# cellular.net
KiCad netlist of a schematic drawn in Altium Designer
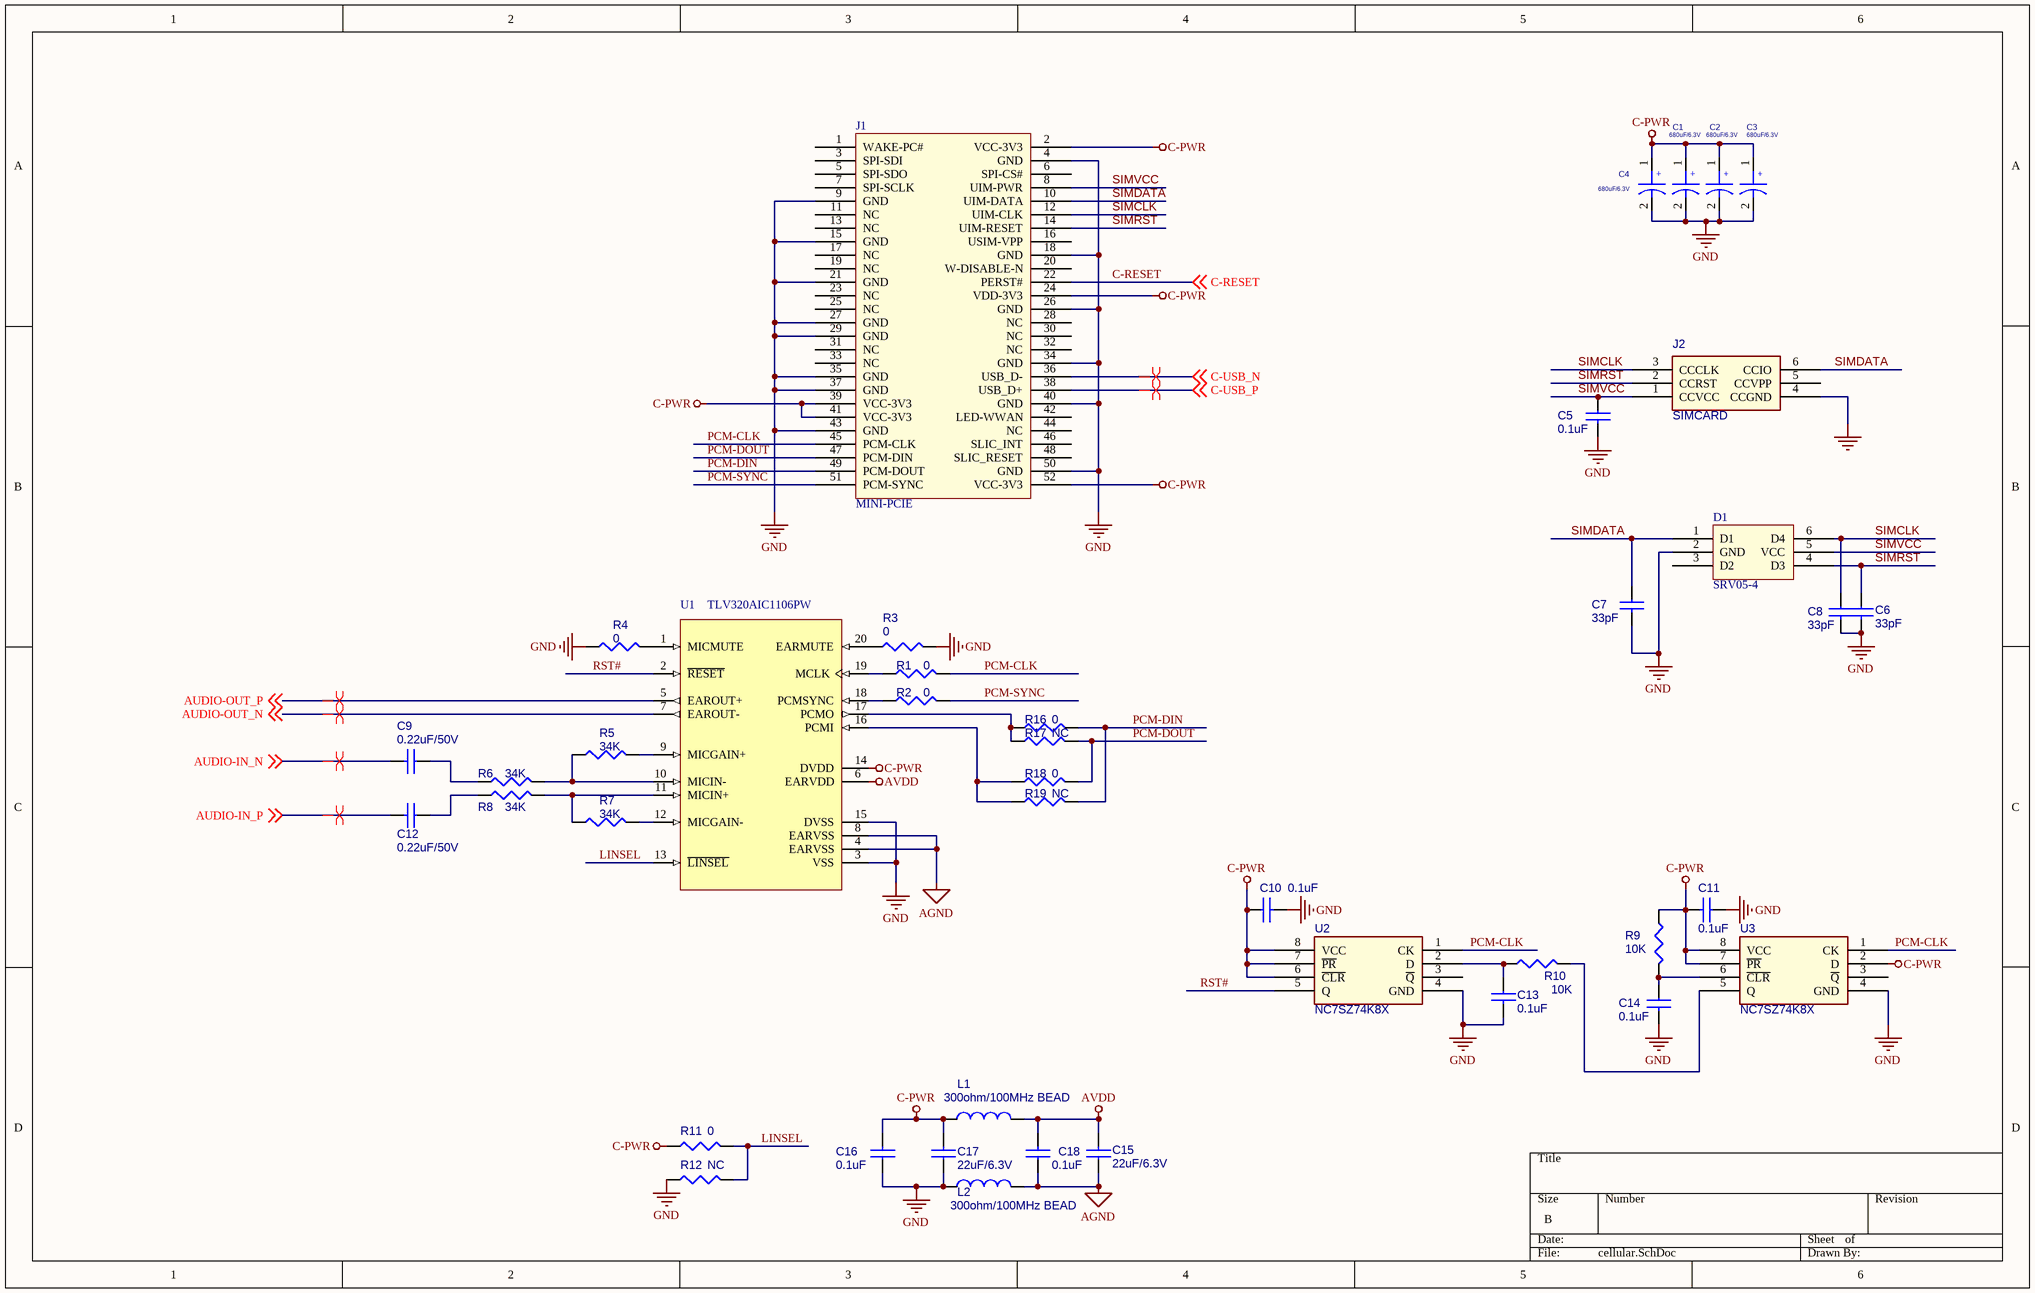
[diagram p0: cellular.SchDoc]

(export (version "E")
  (design (tool "Eeschema 10.0.6"))
  (components
    (comp (ref "C1")
      (value "680uF/6.3V")
      (footprint "7343")
      (description "CAP;10U  ,TT,20V ,20%,6032,SMT")
      (libsource (lib "*") (part "10U-6032-20V"))
    )
    (comp (ref "C2")
      (value "680uF/6.3V")
      (footprint "7343")
      (description "CAP;10U  ,TT,20V ,20%,6032,SMT")
      (libsource (lib "*") (part "10U-6032-20V"))
    )
    (comp (ref "C3")
      (value "680uF/6.3V")
      (footprint "7343")
      (description "CAP;10U  ,TT,20V ,20%,6032,SMT")
      (libsource (lib "*") (part "10U-6032-20V"))
    )
    (comp (ref "C4")
      (value "680uF/6.3V")
      (footprint "7343")
      (description "CAP;10U  ,TT,20V ,20%,6032,SMT")
      (libsource (lib "*") (part "10U-6032-20V"))
    )
    (comp (ref "C5") (value "0.1uF") (libsource (lib "*") (part "P_CAP NP")))
    (comp (ref "C6") (value "33pF") (libsource (lib "*") (part "P_CAP NP")))
    (comp (ref "C7") (value "33pF") (libsource (lib "*") (part "P_CAP NP")))
    (comp (ref "C8") (value "33pF") (libsource (lib "*") (part "P_CAP NP")))
    (comp (ref "C9") (value "0.22uF/50V") (footprint "0603") (libsource (lib "*") (part "P_CAP NP")))
    (comp (ref "C10") (value "0.1uF") (libsource (lib "*") (part "P_CAP NP")))
    (comp (ref "C11") (value "0.1uF") (libsource (lib "*") (part "P_CAP NP")))
    (comp (ref "C12") (value "0.22uF/50V") (footprint "0603") (libsource (lib "*") (part "P_CAP NP")))
    (comp (ref "C13") (value "0.1uF") (libsource (lib "*") (part "P_CAP NP")))
    (comp (ref "C14") (value "0.1uF") (libsource (lib "*") (part "P_CAP NP")))
    (comp (ref "C15") (value "22uF/6.3V") (libsource (lib "*") (part "P_CAP NP")))
    (comp (ref "C16") (value "0.1uF") (libsource (lib "*") (part "P_CAP NP")))
    (comp (ref "C17") (value "22uF/6.3V") (libsource (lib "*") (part "P_CAP NP")))
    (comp (ref "C18") (value "0.1uF") (libsource (lib "*") (part "P_CAP NP")))
    (comp (ref "D1") (value "SRV05-4") (footprint "SOT23-6") (libsource (lib "Schlib") (part "SRV05-4")))
    (comp (ref "J1") (value "MINI-PCIE") (libsource (lib "Schlib") (part "MINI-PCIE")))
    (comp (ref "J2") (value "SIMCARD") (footprint "SIMLOCK") (libsource (lib "*") (part "SIMCARD")))
    (comp (ref "L1") (value "300ohm/100MHz BEAD") (libsource (lib "*") (part "INDUCTOR_4")))
    (comp (ref "L2") (value "300ohm/100MHz BEAD") (libsource (lib "*") (part "INDUCTOR_4")))
    (comp (ref "R1") (value "0") (footprint "0603") (libsource (lib "*") (part "P_R")))
    (comp (ref "R2") (value "0") (footprint "0603") (libsource (lib "*") (part "P_R")))
    (comp (ref "R3") (value "0") (footprint "0603") (libsource (lib "*") (part "P_R")))
    (comp (ref "R4") (value "0") (footprint "0603") (libsource (lib "*") (part "P_R")))
    (comp (ref "R5") (value "34K") (footprint "0603") (libsource (lib "*") (part "P_R")))
    (comp (ref "R6") (value "34K") (footprint "0603") (libsource (lib "*") (part "P_R")))
    (comp (ref "R7") (value "34K") (footprint "0603") (libsource (lib "*") (part "P_R")))
    (comp (ref "R8") (value "34K") (footprint "0603") (libsource (lib "*") (part "P_R")))
    (comp (ref "R9") (value "10K") (footprint "0603") (libsource (lib "*") (part "P_R")))
    (comp (ref "R10") (value "10K") (footprint "0603") (libsource (lib "*") (part "P_R")))
    (comp (ref "R11") (value "0") (footprint "0603") (libsource (lib "*") (part "P_R")))
    (comp (ref "R12") (value "NC") (footprint "0603") (libsource (lib "*") (part "P_R")))
    (comp (ref "R16") (value "0") (footprint "0603") (libsource (lib "*") (part "P_R")))
    (comp (ref "R17") (value "NC") (footprint "0603") (libsource (lib "*") (part "P_R")))
    (comp (ref "R18") (value "0") (footprint "0603") (libsource (lib "*") (part "P_R")))
    (comp (ref "R19") (value "NC") (footprint "0603") (libsource (lib "*") (part "P_R")))
    (comp (ref "U1")
      (value "TLV320AIC1106PW")
      (footprint "PW020")
      (description "PCM CODEC With Microphone Amps & Speaker Driver, 20-Pin TSSOP")
      (fields (field (name "PUBLISHER") "Altium Limited"))
      (libsource (lib "TI Converter CODEC Voice-Band") (part "TLV320AIC1106PWG4"))
    )
    (comp (ref "U2")
      (value "NC7SZ74K8X")
      (footprint "US8")
      (description "IC;NC7SZ74,D-TYPE FLIP-FLOP,US8")
      (libsource (lib "*") (part "NC7SZ74-US8_0"))
    )
    (comp (ref "U3")
      (value "NC7SZ74K8X")
      (footprint "US8")
      (description "IC;NC7SZ74,D-TYPE FLIP-FLOP,US8")
      (libsource (lib "*") (part "NC7SZ74-US8_0"))
    )
  )
  (nets
    (net (code "1") (name "/LINSEL") (class "Default")
      (node (ref "R11") (pin "1") (pinfunction "1_1") (pintype "passive"))
      (node (ref "R12") (pin "1") (pinfunction "1_1") (pintype "passive"))
      (node (ref "U1") (pin "13") (pinfunction "~{LINSEL}_13") (pintype "input"))
    )
    (net (code "2") (name "/PCM-CLK") (class "Default")
      (node (ref "J1") (pin "45") (pinfunction "PCM-CLK_45") (pintype "passive"))
      (node (ref "R1") (pin "1") (pinfunction "1_1") (pintype "passive"))
      (node (ref "U2") (pin "1") (pinfunction "CK_1") (pintype "passive"))
      (node (ref "U3") (pin "1") (pinfunction "CK_1") (pintype "passive"))
    )
    (net (code "3") (name "/PCM-DIN") (class "Default")
      (node (ref "J1") (pin "49") (pinfunction "PCM-DOUT_49") (pintype "passive"))
      (node (ref "R16") (pin "1") (pinfunction "1_1") (pintype "passive"))
      (node (ref "R19") (pin "1") (pinfunction "1_1") (pintype "passive"))
    )
    (net (code "4") (name "/PCM-DOUT") (class "Default")
      (node (ref "J1") (pin "47") (pinfunction "PCM-DIN_47") (pintype "passive"))
      (node (ref "R17") (pin "1") (pinfunction "1_1") (pintype "passive"))
      (node (ref "R18") (pin "1") (pinfunction "1_1") (pintype "passive"))
    )
    (net (code "5") (name "/PCM-SYNC") (class "Default")
      (node (ref "J1") (pin "51") (pinfunction "PCM-SYNC_51") (pintype "passive"))
      (node (ref "R2") (pin "1") (pinfunction "1_1") (pintype "passive"))
    )
    (net (code "6") (name "/RST#") (class "Default")
      (node (ref "U1") (pin "2") (pinfunction "~{RESET}_2") (pintype "input"))
      (node (ref "U2") (pin "5") (pinfunction "Q_5") (pintype "passive"))
    )
    (net (code "7") (name "/SIMCLK") (class "Default")
      (node (ref "C8") (pin "1") (pinfunction "1_1") (pintype "passive"))
      (node (ref "D1") (pin "6") (pinfunction "D4_6") (pintype "passive"))
      (node (ref "J1") (pin "12") (pinfunction "UIM-CLK_12") (pintype "passive"))
      (node (ref "J2") (pin "3") (pinfunction "CCCLK_3") (pintype "passive"))
    )
    (net (code "8") (name "/SIMDATA") (class "Default")
      (node (ref "C7") (pin "1") (pinfunction "1_1") (pintype "passive"))
      (node (ref "D1") (pin "1") (pinfunction "D1_1") (pintype "passive"))
      (node (ref "J1") (pin "10") (pinfunction "UIM-DATA_10") (pintype "passive"))
      (node (ref "J2") (pin "6") (pinfunction "CCIO_6") (pintype "passive"))
    )
    (net (code "9") (name "/SIMRST") (class "Default")
      (node (ref "C6") (pin "1") (pinfunction "1_1") (pintype "passive"))
      (node (ref "D1") (pin "4") (pinfunction "D3_4") (pintype "passive"))
      (node (ref "J1") (pin "14") (pinfunction "UIM-RESET_14") (pintype "passive"))
      (node (ref "J2") (pin "2") (pinfunction "CCRST_2") (pintype "passive"))
    )
    (net (code "10") (name "/SIMVCC") (class "Default")
      (node (ref "C5") (pin "1") (pinfunction "1_1") (pintype "passive"))
      (node (ref "D1") (pin "5") (pinfunction "VCC_5") (pintype "passive"))
      (node (ref "J1") (pin "8") (pinfunction "UIM-PWR_8") (pintype "passive"))
      (node (ref "J2") (pin "1") (pinfunction "CCVCC_1") (pintype "passive"))
    )
    (net (code "11") (name "AGND") (class "Default")
      (node (ref "C15") (pin "1") (pinfunction "1_1") (pintype "passive"))
      (node (ref "C18") (pin "1") (pinfunction "1_1") (pintype "passive"))
      (node (ref "L2") (pin "1") (pinfunction "1_1") (pintype "passive"))
      (node (ref "U1") (pin "4") (pinfunction "EARVSS_4") (pintype "power_in"))
      (node (ref "U1") (pin "8") (pinfunction "EARVSS_8") (pintype "power_in"))
    )
    (net (code "12") (name "AUDIO-IN_N") (class "Default")
      (node (ref "C9") (pin "2") (pinfunction "2_2") (pintype "passive"))
    )
    (net (code "13") (name "AUDIO-IN_P") (class "Default")
      (node (ref "C12") (pin "2") (pinfunction "2_2") (pintype "passive"))
    )
    (net (code "14") (name "AUDIO-OUT_N") (class "Default")
      (node (ref "U1") (pin "7") (pinfunction "EAROUT-_7") (pintype "output"))
    )
    (net (code "15") (name "AUDIO-OUT_P") (class "Default")
      (node (ref "U1") (pin "5") (pinfunction "EAROUT+_5") (pintype "output"))
    )
    (net (code "16") (name "AVDD") (class "Default")
      (node (ref "C15") (pin "2") (pinfunction "2_2") (pintype "passive"))
      (node (ref "C18") (pin "2") (pinfunction "2_2") (pintype "passive"))
      (node (ref "L1") (pin "1") (pinfunction "1_1") (pintype "passive"))
      (node (ref "U1") (pin "6") (pinfunction "EARVDD_6") (pintype "power_in"))
    )
    (net (code "17") (name "C-PWR") (class "Default")
      (node (ref "C1") (pin "1") (pinfunction "1_1") (pintype "passive"))
      (node (ref "C10") (pin "1") (pinfunction "1_1") (pintype "passive"))
      (node (ref "C11") (pin "2") (pinfunction "2_2") (pintype "passive"))
      (node (ref "C16") (pin "2") (pinfunction "2_2") (pintype "passive"))
      (node (ref "C17") (pin "2") (pinfunction "2_2") (pintype "passive"))
      (node (ref "C2") (pin "1") (pinfunction "1_1") (pintype "passive"))
      (node (ref "C3") (pin "1") (pinfunction "1_1") (pintype "passive"))
      (node (ref "C4") (pin "1") (pinfunction "1_1") (pintype "passive"))
      (node (ref "J1") (pin "2") (pinfunction "VCC-3V3_2") (pintype "passive"))
      (node (ref "J1") (pin "24") (pinfunction "VDD-3V3_24") (pintype "passive"))
      (node (ref "J1") (pin "39") (pinfunction "VCC-3V3_39") (pintype "passive"))
      (node (ref "J1") (pin "41") (pinfunction "VCC-3V3_41") (pintype "passive"))
      (node (ref "J1") (pin "52") (pinfunction "VCC-3V3_52") (pintype "passive"))
      (node (ref "L1") (pin "2") (pinfunction "2_2") (pintype "passive"))
      (node (ref "R11") (pin "2") (pinfunction "2_2") (pintype "passive"))
      (node (ref "R9") (pin "2") (pinfunction "2_2") (pintype "passive"))
      (node (ref "U1") (pin "14") (pinfunction "DVDD_14") (pintype "power_in"))
      (node (ref "U2") (pin "6") (pinfunction "~{CLR}_6") (pintype "passive"))
      (node (ref "U2") (pin "7") (pinfunction "~{PR}_7") (pintype "passive"))
      (node (ref "U2") (pin "8") (pinfunction "VCC_8") (pintype "passive"))
      (node (ref "U3") (pin "2") (pinfunction "D_2") (pintype "passive"))
      (node (ref "U3") (pin "7") (pinfunction "~{PR}_7") (pintype "passive"))
      (node (ref "U3") (pin "8") (pinfunction "VCC_8") (pintype "passive"))
    )
    (net (code "18") (name "C-RESET") (class "Default")
      (node (ref "J1") (pin "22") (pinfunction "PERST#_22") (pintype "passive"))
    )
    (net (code "19") (name "C-USB_N") (class "Default")
      (node (ref "J1") (pin "36") (pinfunction "USB_D-_36") (pintype "passive"))
    )
    (net (code "20") (name "C-USB_P") (class "Default")
      (node (ref "J1") (pin "38") (pinfunction "USB_D+_38") (pintype "passive"))
    )
    (net (code "21") (name "GND") (class "Default")
      (node (ref "C1") (pin "2") (pinfunction "2_2") (pintype "passive"))
      (node (ref "C10") (pin "2") (pinfunction "2_2") (pintype "passive"))
      (node (ref "C11") (pin "1") (pinfunction "1_1") (pintype "passive"))
      (node (ref "C13") (pin "2") (pinfunction "2_2") (pintype "passive"))
      (node (ref "C14") (pin "2") (pinfunction "2_2") (pintype "passive"))
      (node (ref "C16") (pin "1") (pinfunction "1_1") (pintype "passive"))
      (node (ref "C17") (pin "1") (pinfunction "1_1") (pintype "passive"))
      (node (ref "C2") (pin "2") (pinfunction "2_2") (pintype "passive"))
      (node (ref "C3") (pin "2") (pinfunction "2_2") (pintype "passive"))
      (node (ref "C4") (pin "2") (pinfunction "2_2") (pintype "passive"))
      (node (ref "C5") (pin "2") (pinfunction "2_2") (pintype "passive"))
      (node (ref "C6") (pin "2") (pinfunction "2_2") (pintype "passive"))
      (node (ref "C7") (pin "2") (pinfunction "2_2") (pintype "passive"))
      (node (ref "C8") (pin "2") (pinfunction "2_2") (pintype "passive"))
      (node (ref "D1") (pin "2") (pinfunction "GND_2") (pintype "passive"))
      (node (ref "J1") (pin "15") (pinfunction "GND_15") (pintype "passive"))
      (node (ref "J1") (pin "18") (pinfunction "GND_18") (pintype "passive"))
      (node (ref "J1") (pin "21") (pinfunction "GND_21") (pintype "passive"))
      (node (ref "J1") (pin "26") (pinfunction "GND_26") (pintype "passive"))
      (node (ref "J1") (pin "27") (pinfunction "GND_27") (pintype "passive"))
      (node (ref "J1") (pin "29") (pinfunction "GND_29") (pintype "passive"))
      (node (ref "J1") (pin "34") (pinfunction "GND_34") (pintype "passive"))
      (node (ref "J1") (pin "35") (pinfunction "GND_35") (pintype "passive"))
      (node (ref "J1") (pin "37") (pinfunction "GND_37") (pintype "passive"))
      (node (ref "J1") (pin "4") (pinfunction "GND_4") (pintype "passive"))
      (node (ref "J1") (pin "40") (pinfunction "GND_40") (pintype "passive"))
      (node (ref "J1") (pin "43") (pinfunction "GND_43") (pintype "passive"))
      (node (ref "J1") (pin "50") (pinfunction "GND_50") (pintype "passive"))
      (node (ref "J1") (pin "9") (pinfunction "GND_9") (pintype "passive"))
      (node (ref "J2") (pin "4") (pinfunction "CCGND_4") (pintype "passive"))
      (node (ref "L2") (pin "2") (pinfunction "2_2") (pintype "passive"))
      (node (ref "R12") (pin "2") (pinfunction "2_2") (pintype "passive"))
      (node (ref "R3") (pin "1") (pinfunction "1_1") (pintype "passive"))
      (node (ref "R4") (pin "2") (pinfunction "2_2") (pintype "passive"))
      (node (ref "U1") (pin "15") (pinfunction "DVSS_15") (pintype "power_in"))
      (node (ref "U1") (pin "3") (pinfunction "VSS_3") (pintype "power_in"))
      (node (ref "U2") (pin "4") (pinfunction "GND_4") (pintype "passive"))
      (node (ref "U3") (pin "4") (pinfunction "GND_4") (pintype "passive"))
    )
    (net (code "22") (name "Net-(C9-Pad1)") (class "Default")
      (node (ref "C9") (pin "1") (pinfunction "1_1") (pintype "passive"))
      (node (ref "R6") (pin "2") (pinfunction "2_2") (pintype "passive"))
    )
    (net (code "23") (name "Net-(C12-Pad1)") (class "Default")
      (node (ref "C12") (pin "1") (pinfunction "1_1") (pintype "passive"))
      (node (ref "R8") (pin "2") (pinfunction "2_2") (pintype "passive"))
    )
    (net (code "24") (name "Net-(U1-EARMUTE)") (class "Default")
      (node (ref "R3") (pin "2") (pinfunction "2_2") (pintype "passive"))
      (node (ref "U1") (pin "20") (pinfunction "EARMUTE_20") (pintype "input"))
    )
    (net (code "25") (name "Net-(U1-MCLK)") (class "Default")
      (node (ref "R1") (pin "2") (pinfunction "2_2") (pintype "passive"))
      (node (ref "U1") (pin "19") (pinfunction "MCLK_19") (pintype "input"))
    )
    (net (code "26") (name "Net-(U1-MICGAIN+)") (class "Default")
      (node (ref "R5") (pin "1") (pinfunction "1_1") (pintype "passive"))
      (node (ref "U1") (pin "9") (pinfunction "MICGAIN+_9") (pintype "input"))
    )
    (net (code "27") (name "Net-(U1-MICGAIN-)") (class "Default")
      (node (ref "R7") (pin "1") (pinfunction "1_1") (pintype "passive"))
      (node (ref "U1") (pin "12") (pinfunction "MICGAIN-_12") (pintype "input"))
    )
    (net (code "28") (name "Net-(U1-MICIN+)") (class "Default")
      (node (ref "R7") (pin "2") (pinfunction "2_2") (pintype "passive"))
      (node (ref "R8") (pin "1") (pinfunction "1_1") (pintype "passive"))
      (node (ref "U1") (pin "11") (pinfunction "MICIN+_11") (pintype "input"))
    )
    (net (code "29") (name "Net-(U1-MICIN-)") (class "Default")
      (node (ref "R5") (pin "2") (pinfunction "2_2") (pintype "passive"))
      (node (ref "R6") (pin "1") (pinfunction "1_1") (pintype "passive"))
      (node (ref "U1") (pin "10") (pinfunction "MICIN-_10") (pintype "input"))
    )
    (net (code "30") (name "Net-(U1-MICMUTE)") (class "Default")
      (node (ref "R4") (pin "1") (pinfunction "1_1") (pintype "passive"))
      (node (ref "U1") (pin "1") (pinfunction "MICMUTE_1") (pintype "input"))
    )
    (net (code "31") (name "Net-(U1-PCMI)") (class "Default")
      (node (ref "R18") (pin "2") (pinfunction "2_2") (pintype "passive"))
      (node (ref "R19") (pin "2") (pinfunction "2_2") (pintype "passive"))
      (node (ref "U1") (pin "16") (pinfunction "PCMI_16") (pintype "input"))
    )
    (net (code "32") (name "Net-(U1-PCMO)") (class "Default")
      (node (ref "R16") (pin "2") (pinfunction "2_2") (pintype "passive"))
      (node (ref "R17") (pin "2") (pinfunction "2_2") (pintype "passive"))
      (node (ref "U1") (pin "17") (pinfunction "PCMO_17") (pintype "output"))
    )
    (net (code "33") (name "Net-(U1-PCMSYNC)") (class "Default")
      (node (ref "R2") (pin "2") (pinfunction "2_2") (pintype "passive"))
      (node (ref "U1") (pin "18") (pinfunction "PCMSYNC_18") (pintype "input"))
    )
    (net (code "34") (name "Net-(U2-D)") (class "Default")
      (node (ref "C13") (pin "1") (pinfunction "1_1") (pintype "passive"))
      (node (ref "R10") (pin "2") (pinfunction "2_2") (pintype "passive"))
      (node (ref "U2") (pin "2") (pinfunction "D_2") (pintype "passive"))
    )
    (net (code "35") (name "Net-(U3-Q)") (class "Default")
      (node (ref "R10") (pin "1") (pinfunction "1_1") (pintype "passive"))
      (node (ref "U3") (pin "5") (pinfunction "Q_5") (pintype "passive"))
    )
    (net (code "36") (name "Net-(U3-~{CLR})") (class "Default")
      (node (ref "C14") (pin "1") (pinfunction "1_1") (pintype "passive"))
      (node (ref "R9") (pin "1") (pinfunction "1_1") (pintype "passive"))
      (node (ref "U3") (pin "6") (pinfunction "~{CLR}_6") (pintype "passive"))
    )
    (net (code "37") (name "unconnected-(D1-D2-Pad3)") (class "Default")
      (node (ref "D1") (pin "3") (pinfunction "D2_3") (pintype "passive"))
    )
    (net (code "38") (name "unconnected-(J1-LED-WWAN-Pad42)") (class "Default")
      (node (ref "J1") (pin "42") (pinfunction "LED-WWAN_42") (pintype "passive"))
    )
    (net (code "39") (name "unconnected-(J1-NC-Pad11)") (class "Default")
      (node (ref "J1") (pin "11") (pinfunction "NC_11") (pintype "passive"))
    )
    (net (code "40") (name "unconnected-(J1-NC-Pad13)") (class "Default")
      (node (ref "J1") (pin "13") (pinfunction "NC_13") (pintype "passive"))
    )
    (net (code "41") (name "unconnected-(J1-NC-Pad17)") (class "Default")
      (node (ref "J1") (pin "17") (pinfunction "NC_17") (pintype "passive"))
    )
    (net (code "42") (name "unconnected-(J1-NC-Pad19)") (class "Default")
      (node (ref "J1") (pin "19") (pinfunction "NC_19") (pintype "passive"))
    )
    (net (code "43") (name "unconnected-(J1-NC-Pad23)") (class "Default")
      (node (ref "J1") (pin "23") (pinfunction "NC_23") (pintype "passive"))
    )
    (net (code "44") (name "unconnected-(J1-NC-Pad25)") (class "Default")
      (node (ref "J1") (pin "25") (pinfunction "NC_25") (pintype "passive"))
    )
    (net (code "45") (name "unconnected-(J1-NC-Pad28)") (class "Default")
      (node (ref "J1") (pin "28") (pinfunction "NC_28") (pintype "passive"))
    )
    (net (code "46") (name "unconnected-(J1-NC-Pad30)") (class "Default")
      (node (ref "J1") (pin "30") (pinfunction "NC_30") (pintype "passive"))
    )
    (net (code "47") (name "unconnected-(J1-NC-Pad31)") (class "Default")
      (node (ref "J1") (pin "31") (pinfunction "NC_31") (pintype "passive"))
    )
    (net (code "48") (name "unconnected-(J1-NC-Pad32)") (class "Default")
      (node (ref "J1") (pin "32") (pinfunction "NC_32") (pintype "passive"))
    )
    (net (code "49") (name "unconnected-(J1-NC-Pad33)") (class "Default")
      (node (ref "J1") (pin "33") (pinfunction "NC_33") (pintype "passive"))
    )
    (net (code "50") (name "unconnected-(J1-NC-Pad44)") (class "Default")
      (node (ref "J1") (pin "44") (pinfunction "NC_44") (pintype "passive"))
    )
    (net (code "51") (name "unconnected-(J1-SLIC_INT-Pad46)") (class "Default")
      (node (ref "J1") (pin "46") (pinfunction "SLIC_INT_46") (pintype "passive"))
    )
    (net (code "52") (name "unconnected-(J1-SLIC_RESET-Pad48)") (class "Default")
      (node (ref "J1") (pin "48") (pinfunction "SLIC_RESET_48") (pintype "passive"))
    )
    (net (code "53") (name "unconnected-(J1-SPI-CS#-Pad6)") (class "Default")
      (node (ref "J1") (pin "6") (pinfunction "SPI-CS#_6") (pintype "passive"))
    )
    (net (code "54") (name "unconnected-(J1-SPI-SCLK-Pad7)") (class "Default")
      (node (ref "J1") (pin "7") (pinfunction "SPI-SCLK_7") (pintype "passive"))
    )
    (net (code "55") (name "unconnected-(J1-SPI-SDI-Pad3)") (class "Default")
      (node (ref "J1") (pin "3") (pinfunction "SPI-SDI_3") (pintype "passive"))
    )
    (net (code "56") (name "unconnected-(J1-SPI-SDO-Pad5)") (class "Default")
      (node (ref "J1") (pin "5") (pinfunction "SPI-SDO_5") (pintype "passive"))
    )
    (net (code "57") (name "unconnected-(J1-USIM-VPP-Pad16)") (class "Default")
      (node (ref "J1") (pin "16") (pinfunction "USIM-VPP_16") (pintype "passive"))
    )
    (net (code "58") (name "unconnected-(J1-W-DISABLE-N-Pad20)") (class "Default")
      (node (ref "J1") (pin "20") (pinfunction "W-DISABLE-N_20") (pintype "passive"))
    )
    (net (code "59") (name "unconnected-(J1-WAKE-PC#-Pad1)") (class "Default")
      (node (ref "J1") (pin "1") (pinfunction "WAKE-PC#_1") (pintype "passive"))
    )
    (net (code "60") (name "unconnected-(J2-CCVPP-Pad5)") (class "Default")
      (node (ref "J2") (pin "5") (pinfunction "CCVPP_5") (pintype "passive"))
    )
    (net (code "61") (name "unconnected-(U2-~{Q}-Pad3)") (class "Default")
      (node (ref "U2") (pin "3") (pinfunction "~{Q}_3") (pintype "passive"))
    )
    (net (code "62") (name "unconnected-(U3-~{Q}-Pad3)") (class "Default")
      (node (ref "U3") (pin "3") (pinfunction "~{Q}_3") (pintype "passive"))
    )
  )
)
